# Mega_Shield-v13.net
KiCad netlist of a schematic drawn in EAGLE
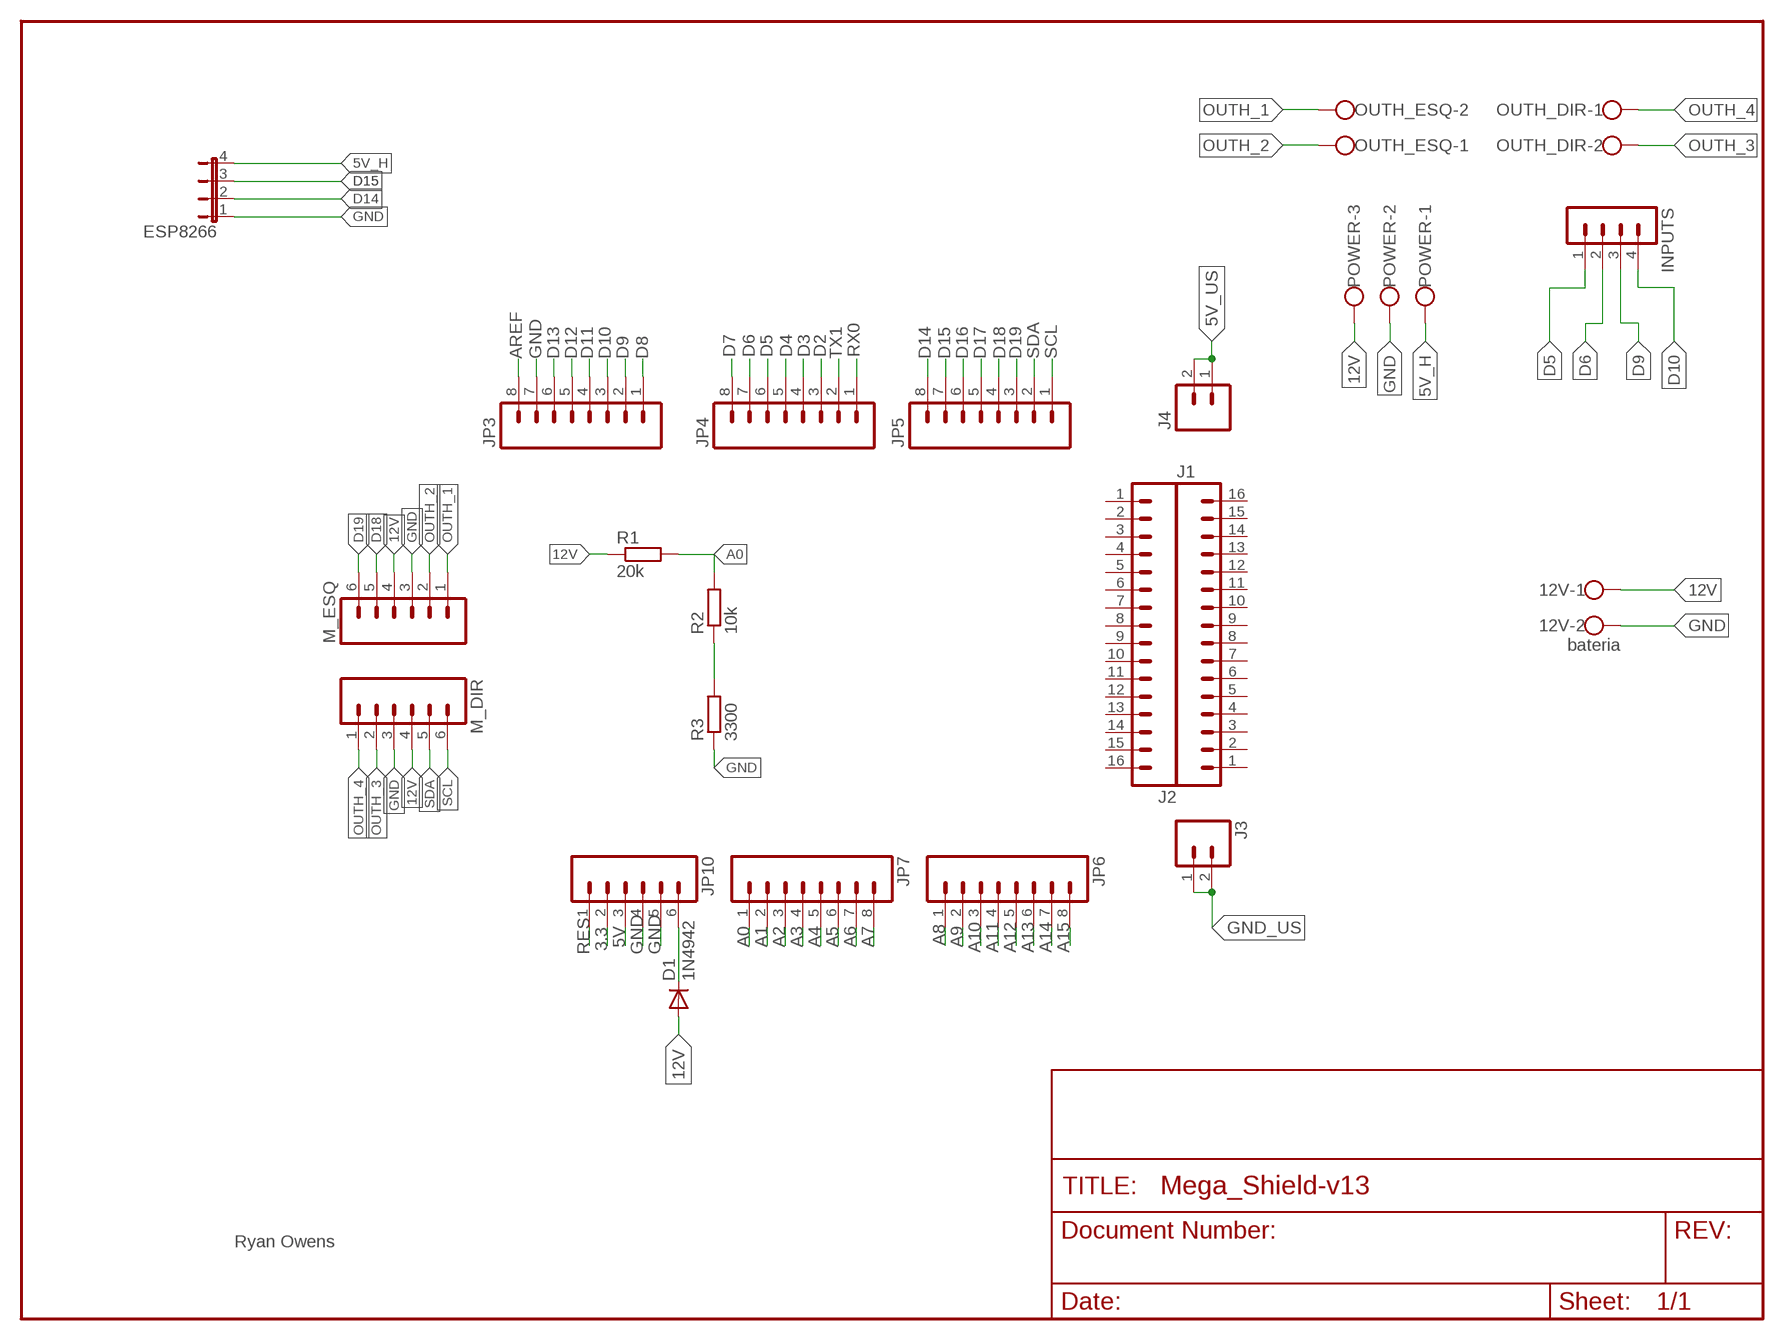
[diagram p0: schematic, sheet 1]

(export (version "E")
  (design (tool "Eeschema 10.0.6"))
  (components
    (comp (ref "12V")
      (value "bateria")
      (footprint "eagle-import:W237-102")
      (fields (field (name "MPN") "237-102"))
      (libsource (lib "eagle-import") (part "W237-102"))
    )
    (comp (ref "D1")
      (value "1N4942")
      (footprint "eagle-import:DO41-10")
      (libsource (lib "eagle-import") (part "1N4942"))
    )
    (comp (ref "ESP8266")
      (value "JP4E")
      (footprint "eagle-import:JP4")
      (libsource (lib "eagle-import") (part "JP4E"))
    )
    (comp (ref "INPUTS")
      (value "MA04-1")
      (footprint "eagle-import:MA04-1")
      (libsource (lib "eagle-import") (part "MA04-1"))
    )
    (comp (ref "J1")
      (value "M16LOCK")
      (footprint "eagle-import:1X16_LOCK")
      (libsource (lib "eagle-import") (part "M16LOCK"))
    )
    (comp (ref "J2")
      (value "M16LOCK")
      (footprint "eagle-import:1X16_LOCK")
      (libsource (lib "eagle-import") (part "M16LOCK"))
    )
    (comp (ref "J3")
      (value "M02LOCK")
      (footprint "eagle-import:1X02_LOCK")
      (libsource (lib "eagle-import") (part "M02LOCK"))
    )
    (comp (ref "J4")
      (value "M02LOCK")
      (footprint "eagle-import:1X02_LOCK")
      (libsource (lib "eagle-import") (part "M02LOCK"))
    )
    (comp (ref "JP3")
      (value "M08LOCK")
      (footprint "eagle-import:1X08_LOCK")
      (libsource (lib "eagle-import") (part "M08LOCK"))
    )
    (comp (ref "JP4")
      (value "M08LOCK")
      (footprint "eagle-import:1X08_LOCK")
      (libsource (lib "eagle-import") (part "M08LOCK"))
    )
    (comp (ref "JP5")
      (value "M08LOCK")
      (footprint "eagle-import:1X08_LOCK")
      (libsource (lib "eagle-import") (part "M08LOCK"))
    )
    (comp (ref "JP6")
      (value "M08LOCK")
      (footprint "eagle-import:1X08_LOCK")
      (libsource (lib "eagle-import") (part "M08LOCK"))
    )
    (comp (ref "JP7")
      (value "M08LOCK")
      (footprint "eagle-import:1X08_LOCK")
      (libsource (lib "eagle-import") (part "M08LOCK"))
    )
    (comp (ref "JP10")
      (value "M06LOCK")
      (footprint "eagle-import:1X06_LOCK")
      (libsource (lib "eagle-import") (part "M06LOCK"))
    )
    (comp (ref "M_DIR")
      (value "M06LOCK")
      (footprint "eagle-import:1X06_LOCK")
      (libsource (lib "eagle-import") (part "M06LOCK"))
    )
    (comp (ref "M_ESQ")
      (value "M06LOCK")
      (footprint "eagle-import:1X06_LOCK")
      (libsource (lib "eagle-import") (part "M06LOCK"))
    )
    (comp (ref "OUTH_DIR")
      (value "W237-102")
      (footprint "eagle-import:W237-102")
      (fields (field (name "MPN") "237-102"))
      (libsource (lib "eagle-import") (part "W237-102"))
    )
    (comp (ref "OUTH_ESQ")
      (value "W237-102")
      (footprint "eagle-import:W237-102")
      (fields (field (name "MPN") "237-102"))
      (libsource (lib "eagle-import") (part "W237-102"))
    )
    (comp (ref "POWER")
      (value "W237-103")
      (footprint "eagle-import:W237-103")
      (fields (field (name "MPN") "237-103"))
      (libsource (lib "eagle-import") (part "W237-103"))
    )
    (comp (ref "R1")
      (value "20k")
      (footprint "eagle-import:0207_10")
      (libsource (lib "eagle-import") (part "R-EU_0207/10"))
    )
    (comp (ref "R2")
      (value "10k")
      (footprint "eagle-import:0207_10")
      (libsource (lib "eagle-import") (part "R-EU_0207/10"))
    )
    (comp (ref "R3")
      (value "3300")
      (footprint "eagle-import:0207_10")
      (libsource (lib "eagle-import") (part "R-EU_0207/10"))
    )
  )
  (nets
    (net (code "1") (name "/3.3") (class "Default")
      (node (ref "JP10") (pin "2") (pinfunction "2_2") (pintype "passive"))
    )
    (net (code "2") (name "/5V") (class "Default")
      (node (ref "JP10") (pin "3") (pinfunction "3_3") (pintype "passive"))
    )
    (net (code "3") (name "/A1") (class "Default")
      (node (ref "JP7") (pin "2") (pinfunction "2_2") (pintype "passive"))
    )
    (net (code "4") (name "/A2") (class "Default")
      (node (ref "JP7") (pin "3") (pinfunction "3_3") (pintype "passive"))
    )
    (net (code "5") (name "/A3") (class "Default")
      (node (ref "JP7") (pin "4") (pinfunction "4_4") (pintype "passive"))
    )
    (net (code "6") (name "/A4") (class "Default")
      (node (ref "JP7") (pin "5") (pinfunction "5_5") (pintype "passive"))
    )
    (net (code "7") (name "/A5") (class "Default")
      (node (ref "JP7") (pin "6") (pinfunction "6_6") (pintype "passive"))
    )
    (net (code "8") (name "/A6") (class "Default")
      (node (ref "JP7") (pin "7") (pinfunction "7_7") (pintype "passive"))
    )
    (net (code "9") (name "/A7") (class "Default")
      (node (ref "JP7") (pin "8") (pinfunction "8_8") (pintype "passive"))
    )
    (net (code "10") (name "/A8") (class "Default")
      (node (ref "JP6") (pin "1") (pinfunction "1_1") (pintype "passive"))
    )
    (net (code "11") (name "/A9") (class "Default")
      (node (ref "JP6") (pin "2") (pinfunction "2_2") (pintype "passive"))
    )
    (net (code "12") (name "/A10") (class "Default")
      (node (ref "JP6") (pin "3") (pinfunction "3_3") (pintype "passive"))
    )
    (net (code "13") (name "/A11") (class "Default")
      (node (ref "JP6") (pin "4") (pinfunction "4_4") (pintype "passive"))
    )
    (net (code "14") (name "/A12") (class "Default")
      (node (ref "JP6") (pin "5") (pinfunction "5_5") (pintype "passive"))
    )
    (net (code "15") (name "/A13") (class "Default")
      (node (ref "JP6") (pin "6") (pinfunction "6_6") (pintype "passive"))
    )
    (net (code "16") (name "/A14") (class "Default")
      (node (ref "JP6") (pin "7") (pinfunction "7_7") (pintype "passive"))
    )
    (net (code "17") (name "/A15") (class "Default")
      (node (ref "JP6") (pin "8") (pinfunction "8_8") (pintype "passive"))
    )
    (net (code "18") (name "/AREF") (class "Default")
      (node (ref "JP3") (pin "8") (pinfunction "8_8") (pintype "passive"))
    )
    (net (code "19") (name "/D2") (class "Default")
      (node (ref "JP4") (pin "3") (pinfunction "3_3") (pintype "passive"))
    )
    (net (code "20") (name "/D3") (class "Default")
      (node (ref "JP4") (pin "4") (pinfunction "4_4") (pintype "passive"))
    )
    (net (code "21") (name "/D4") (class "Default")
      (node (ref "JP4") (pin "5") (pinfunction "5_5") (pintype "passive"))
    )
    (net (code "22") (name "/D7") (class "Default")
      (node (ref "JP4") (pin "8") (pinfunction "8_8") (pintype "passive"))
    )
    (net (code "23") (name "/D8") (class "Default")
      (node (ref "JP3") (pin "1") (pinfunction "1_1") (pintype "passive"))
    )
    (net (code "24") (name "/D11") (class "Default")
      (node (ref "JP3") (pin "4") (pinfunction "4_4") (pintype "passive"))
    )
    (net (code "25") (name "/D12") (class "Default")
      (node (ref "JP3") (pin "5") (pinfunction "5_5") (pintype "passive"))
    )
    (net (code "26") (name "/D13") (class "Default")
      (node (ref "JP3") (pin "6") (pinfunction "6_6") (pintype "passive"))
    )
    (net (code "27") (name "/D16") (class "Default")
      (node (ref "JP5") (pin "6") (pinfunction "6_6") (pintype "passive"))
    )
    (net (code "28") (name "/D17") (class "Default")
      (node (ref "JP5") (pin "5") (pinfunction "5_5") (pintype "passive"))
    )
    (net (code "29") (name "/RES") (class "Default")
      (node (ref "JP10") (pin "1") (pinfunction "1_1") (pintype "passive"))
    )
    (net (code "30") (name "/RX0") (class "Default")
      (node (ref "JP4") (pin "1") (pinfunction "1_1") (pintype "passive"))
    )
    (net (code "31") (name "/TX1") (class "Default")
      (node (ref "JP4") (pin "2") (pinfunction "2_2") (pintype "passive"))
    )
    (net (code "32") (name "5V_H") (class "Default")
      (node (ref "ESP8266") (pin "4") (pinfunction "4_4") (pintype "passive"))
      (node (ref "POWER") (pin "1") (pinfunction "KL_1") (pintype "passive"))
    )
    (net (code "33") (name "5V_US") (class "Default")
      (node (ref "J4") (pin "1") (pinfunction "1_1") (pintype "passive"))
      (node (ref "J4") (pin "2") (pinfunction "2_2") (pintype "passive"))
    )
    (net (code "34") (name "12V") (class "Default")
      (node (ref "12V") (pin "1") (pinfunction "KL_1") (pintype "passive"))
      (node (ref "D1") (pin "A") (pinfunction "A_A") (pintype "passive"))
      (node (ref "M_DIR") (pin "4") (pinfunction "4_4") (pintype "passive"))
      (node (ref "M_ESQ") (pin "4") (pinfunction "4_4") (pintype "passive"))
      (node (ref "POWER") (pin "3") (pinfunction "KL_3") (pintype "passive"))
      (node (ref "R1") (pin "1") (pinfunction "1_1") (pintype "passive"))
    )
    (net (code "35") (name "A0") (class "Default")
      (node (ref "JP7") (pin "1") (pinfunction "1_1") (pintype "passive"))
      (node (ref "R1") (pin "2") (pinfunction "2_2") (pintype "passive"))
      (node (ref "R2") (pin "2") (pinfunction "2_2") (pintype "passive"))
    )
    (net (code "36") (name "D5") (class "Default")
      (node (ref "INPUTS") (pin "1") (pinfunction "1_1") (pintype "passive"))
      (node (ref "JP4") (pin "6") (pinfunction "6_6") (pintype "passive"))
    )
    (net (code "37") (name "D6") (class "Default")
      (node (ref "INPUTS") (pin "2") (pinfunction "2_2") (pintype "passive"))
      (node (ref "JP4") (pin "7") (pinfunction "7_7") (pintype "passive"))
    )
    (net (code "38") (name "D9") (class "Default")
      (node (ref "INPUTS") (pin "3") (pinfunction "3_3") (pintype "passive"))
      (node (ref "JP3") (pin "2") (pinfunction "2_2") (pintype "passive"))
    )
    (net (code "39") (name "D10") (class "Default")
      (node (ref "INPUTS") (pin "4") (pinfunction "4_4") (pintype "passive"))
      (node (ref "JP3") (pin "3") (pinfunction "3_3") (pintype "passive"))
    )
    (net (code "40") (name "D14") (class "Default")
      (node (ref "ESP8266") (pin "2") (pinfunction "2_2") (pintype "passive"))
      (node (ref "JP5") (pin "8") (pinfunction "8_8") (pintype "passive"))
    )
    (net (code "41") (name "D15") (class "Default")
      (node (ref "ESP8266") (pin "3") (pinfunction "3_3") (pintype "passive"))
      (node (ref "JP5") (pin "7") (pinfunction "7_7") (pintype "passive"))
    )
    (net (code "42") (name "D18") (class "Default")
      (node (ref "JP5") (pin "4") (pinfunction "4_4") (pintype "passive"))
      (node (ref "M_ESQ") (pin "5") (pinfunction "5_5") (pintype "passive"))
    )
    (net (code "43") (name "D19") (class "Default")
      (node (ref "JP5") (pin "3") (pinfunction "3_3") (pintype "passive"))
      (node (ref "M_ESQ") (pin "6") (pinfunction "6_6") (pintype "passive"))
    )
    (net (code "44") (name "GND") (class "Default")
      (node (ref "12V") (pin "2") (pinfunction "KL_2") (pintype "passive"))
      (node (ref "ESP8266") (pin "1") (pinfunction "1_1") (pintype "passive"))
      (node (ref "JP10") (pin "4") (pinfunction "4_4") (pintype "passive"))
      (node (ref "JP10") (pin "5") (pinfunction "5_5") (pintype "passive"))
      (node (ref "JP3") (pin "7") (pinfunction "7_7") (pintype "passive"))
      (node (ref "M_DIR") (pin "3") (pinfunction "3_3") (pintype "passive"))
      (node (ref "M_ESQ") (pin "3") (pinfunction "3_3") (pintype "passive"))
      (node (ref "POWER") (pin "2") (pinfunction "KL_2") (pintype "passive"))
      (node (ref "R3") (pin "1") (pinfunction "1_1") (pintype "passive"))
    )
    (net (code "45") (name "GND_US") (class "Default")
      (node (ref "J3") (pin "1") (pinfunction "1_1") (pintype "passive"))
      (node (ref "J3") (pin "2") (pinfunction "2_2") (pintype "passive"))
    )
    (net (code "46") (name "Net-(D1-PadC)") (class "Default")
      (node (ref "D1") (pin "C") (pinfunction "C_C") (pintype "passive"))
      (node (ref "JP10") (pin "6") (pinfunction "6_6") (pintype "passive"))
    )
    (net (code "47") (name "Net-(R2-Pad1)") (class "Default")
      (node (ref "R2") (pin "1") (pinfunction "1_1") (pintype "passive"))
      (node (ref "R3") (pin "2") (pinfunction "2_2") (pintype "passive"))
    )
    (net (code "48") (name "OUTH_1") (class "Default")
      (node (ref "M_ESQ") (pin "1") (pinfunction "1_1") (pintype "passive"))
      (node (ref "OUTH_ESQ") (pin "2") (pinfunction "KL_2") (pintype "passive"))
    )
    (net (code "49") (name "OUTH_2") (class "Default")
      (node (ref "M_ESQ") (pin "2") (pinfunction "2_2") (pintype "passive"))
      (node (ref "OUTH_ESQ") (pin "1") (pinfunction "KL_1") (pintype "passive"))
    )
    (net (code "50") (name "OUTH_3") (class "Default")
      (node (ref "M_DIR") (pin "2") (pinfunction "2_2") (pintype "passive"))
      (node (ref "OUTH_DIR") (pin "2") (pinfunction "KL_2") (pintype "passive"))
    )
    (net (code "51") (name "OUTH_4") (class "Default")
      (node (ref "M_DIR") (pin "1") (pinfunction "1_1") (pintype "passive"))
      (node (ref "OUTH_DIR") (pin "1") (pinfunction "KL_1") (pintype "passive"))
    )
    (net (code "52") (name "SCL") (class "Default")
      (node (ref "JP5") (pin "1") (pinfunction "1_1") (pintype "passive"))
      (node (ref "M_DIR") (pin "6") (pinfunction "6_6") (pintype "passive"))
    )
    (net (code "53") (name "SDA") (class "Default")
      (node (ref "JP5") (pin "2") (pinfunction "2_2") (pintype "passive"))
      (node (ref "M_DIR") (pin "5") (pinfunction "5_5") (pintype "passive"))
    )
    (net (code "54") (name "unconnected-(J1-Pad1)") (class "Default")
      (node (ref "J1") (pin "1") (pinfunction "1_1") (pintype "passive"))
    )
    (net (code "55") (name "unconnected-(J1-Pad2)") (class "Default")
      (node (ref "J1") (pin "2") (pinfunction "2_2") (pintype "passive"))
    )
    (net (code "56") (name "unconnected-(J1-Pad3)") (class "Default")
      (node (ref "J1") (pin "3") (pinfunction "3_3") (pintype "passive"))
    )
    (net (code "57") (name "unconnected-(J1-Pad4)") (class "Default")
      (node (ref "J1") (pin "4") (pinfunction "4_4") (pintype "passive"))
    )
    (net (code "58") (name "unconnected-(J1-Pad5)") (class "Default")
      (node (ref "J1") (pin "5") (pinfunction "5_5") (pintype "passive"))
    )
    (net (code "59") (name "unconnected-(J1-Pad6)") (class "Default")
      (node (ref "J1") (pin "6") (pinfunction "6_6") (pintype "passive"))
    )
    (net (code "60") (name "unconnected-(J1-Pad7)") (class "Default")
      (node (ref "J1") (pin "7") (pinfunction "7_7") (pintype "passive"))
    )
    (net (code "61") (name "unconnected-(J1-Pad8)") (class "Default")
      (node (ref "J1") (pin "8") (pinfunction "8_8") (pintype "passive"))
    )
    (net (code "62") (name "unconnected-(J1-Pad9)") (class "Default")
      (node (ref "J1") (pin "9") (pinfunction "9_9") (pintype "passive"))
    )
    (net (code "63") (name "unconnected-(J1-Pad10)") (class "Default")
      (node (ref "J1") (pin "10") (pinfunction "10_10") (pintype "passive"))
    )
    (net (code "64") (name "unconnected-(J1-Pad11)") (class "Default")
      (node (ref "J1") (pin "11") (pinfunction "11_11") (pintype "passive"))
    )
    (net (code "65") (name "unconnected-(J1-Pad12)") (class "Default")
      (node (ref "J1") (pin "12") (pinfunction "12_12") (pintype "passive"))
    )
    (net (code "66") (name "unconnected-(J1-Pad13)") (class "Default")
      (node (ref "J1") (pin "13") (pinfunction "13_13") (pintype "passive"))
    )
    (net (code "67") (name "unconnected-(J1-Pad14)") (class "Default")
      (node (ref "J1") (pin "14") (pinfunction "14_14") (pintype "passive"))
    )
    (net (code "68") (name "unconnected-(J1-Pad15)") (class "Default")
      (node (ref "J1") (pin "15") (pinfunction "15_15") (pintype "passive"))
    )
    (net (code "69") (name "unconnected-(J1-Pad16)") (class "Default")
      (node (ref "J1") (pin "16") (pinfunction "16_16") (pintype "passive"))
    )
    (net (code "70") (name "unconnected-(J2-Pad1)") (class "Default")
      (node (ref "J2") (pin "1") (pinfunction "1_1") (pintype "passive"))
    )
    (net (code "71") (name "unconnected-(J2-Pad2)") (class "Default")
      (node (ref "J2") (pin "2") (pinfunction "2_2") (pintype "passive"))
    )
    (net (code "72") (name "unconnected-(J2-Pad3)") (class "Default")
      (node (ref "J2") (pin "3") (pinfunction "3_3") (pintype "passive"))
    )
    (net (code "73") (name "unconnected-(J2-Pad4)") (class "Default")
      (node (ref "J2") (pin "4") (pinfunction "4_4") (pintype "passive"))
    )
    (net (code "74") (name "unconnected-(J2-Pad5)") (class "Default")
      (node (ref "J2") (pin "5") (pinfunction "5_5") (pintype "passive"))
    )
    (net (code "75") (name "unconnected-(J2-Pad6)") (class "Default")
      (node (ref "J2") (pin "6") (pinfunction "6_6") (pintype "passive"))
    )
    (net (code "76") (name "unconnected-(J2-Pad7)") (class "Default")
      (node (ref "J2") (pin "7") (pinfunction "7_7") (pintype "passive"))
    )
    (net (code "77") (name "unconnected-(J2-Pad8)") (class "Default")
      (node (ref "J2") (pin "8") (pinfunction "8_8") (pintype "passive"))
    )
    (net (code "78") (name "unconnected-(J2-Pad9)") (class "Default")
      (node (ref "J2") (pin "9") (pinfunction "9_9") (pintype "passive"))
    )
    (net (code "79") (name "unconnected-(J2-Pad10)") (class "Default")
      (node (ref "J2") (pin "10") (pinfunction "10_10") (pintype "passive"))
    )
    (net (code "80") (name "unconnected-(J2-Pad11)") (class "Default")
      (node (ref "J2") (pin "11") (pinfunction "11_11") (pintype "passive"))
    )
    (net (code "81") (name "unconnected-(J2-Pad12)") (class "Default")
      (node (ref "J2") (pin "12") (pinfunction "12_12") (pintype "passive"))
    )
    (net (code "82") (name "unconnected-(J2-Pad13)") (class "Default")
      (node (ref "J2") (pin "13") (pinfunction "13_13") (pintype "passive"))
    )
    (net (code "83") (name "unconnected-(J2-Pad14)") (class "Default")
      (node (ref "J2") (pin "14") (pinfunction "14_14") (pintype "passive"))
    )
    (net (code "84") (name "unconnected-(J2-Pad15)") (class "Default")
      (node (ref "J2") (pin "15") (pinfunction "15_15") (pintype "passive"))
    )
    (net (code "85") (name "unconnected-(J2-Pad16)") (class "Default")
      (node (ref "J2") (pin "16") (pinfunction "16_16") (pintype "passive"))
    )
  )
)
